# schematic_1_3.net
KiCad netlist of a schematic drawn in EAGLE
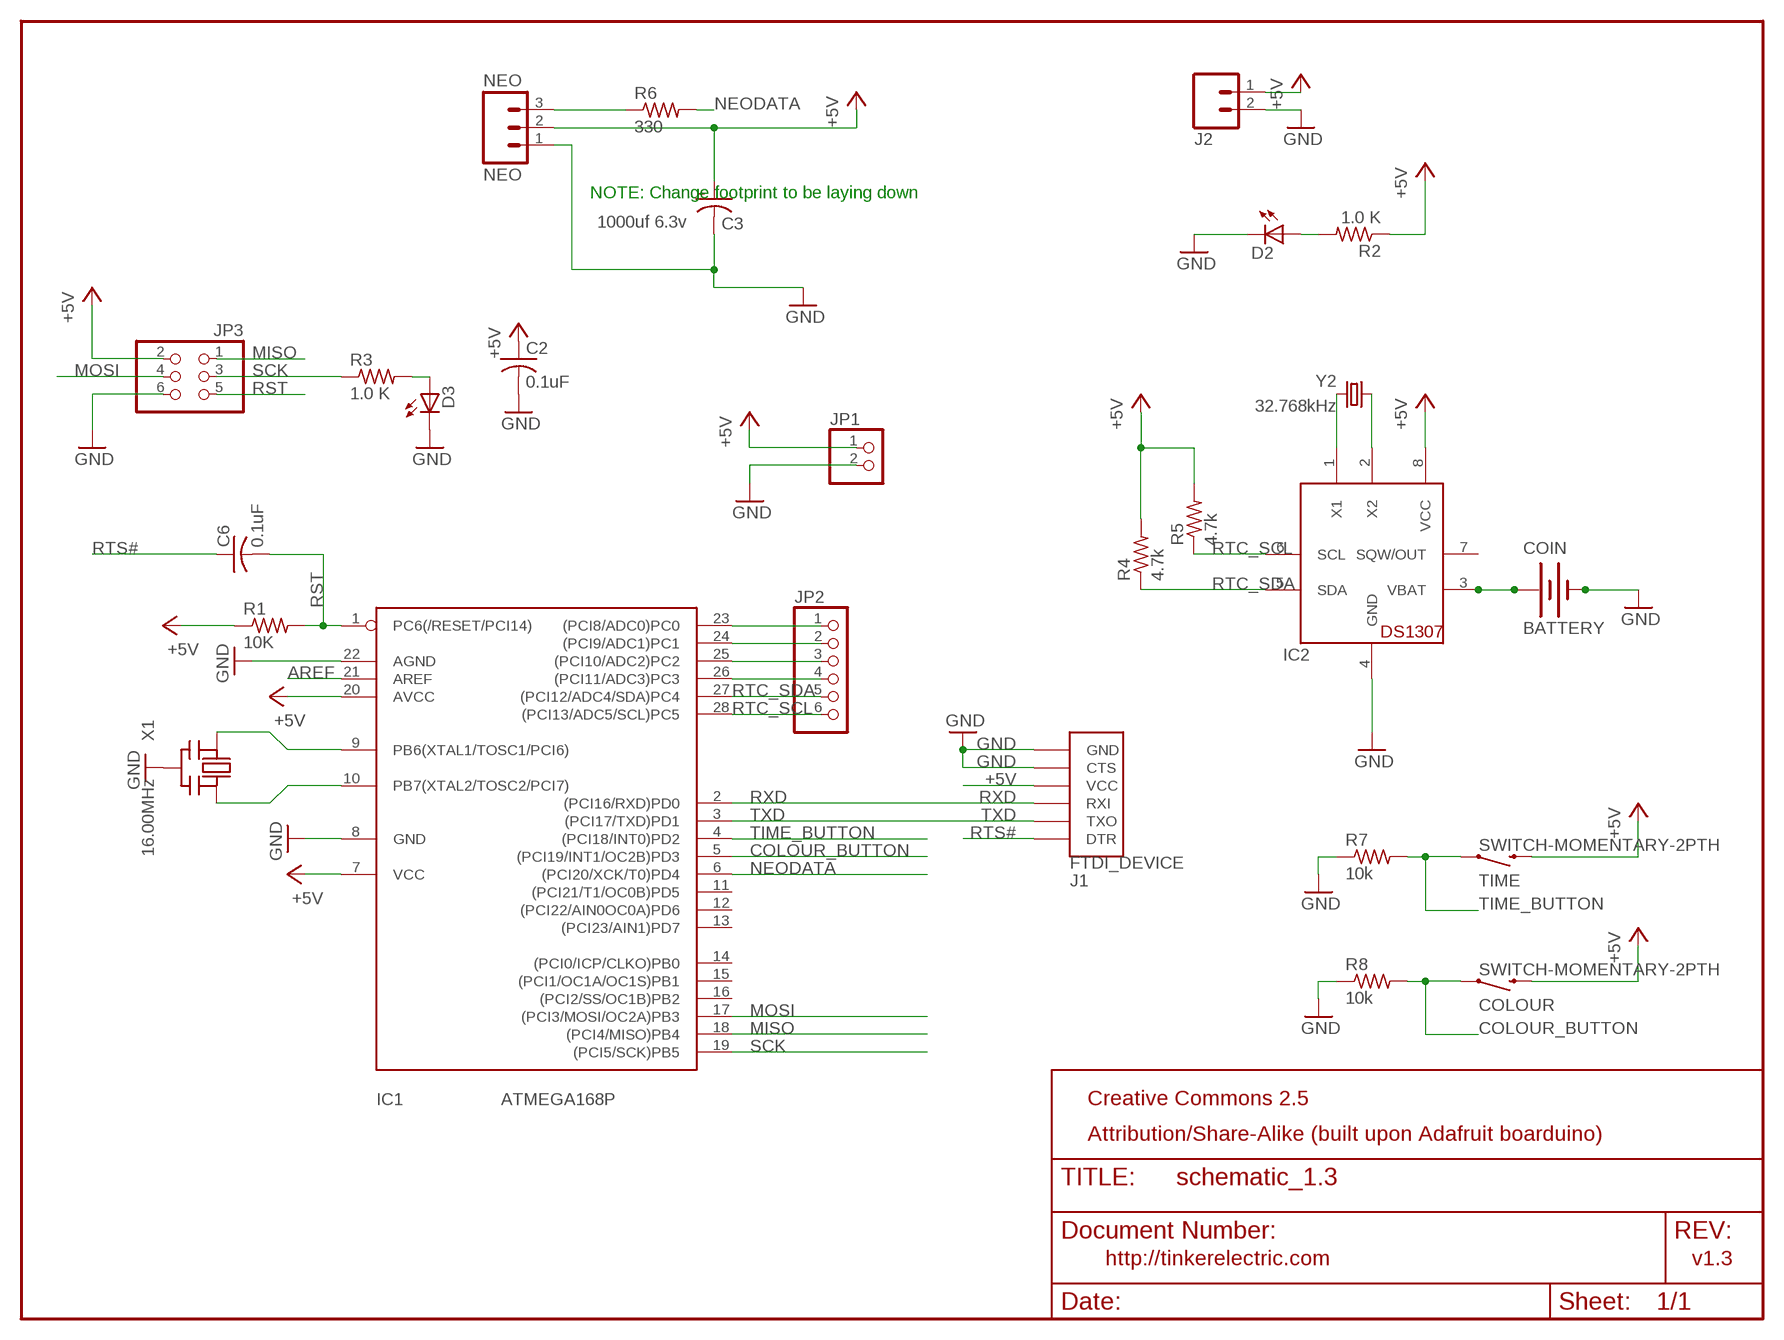
[diagram p0: schematic, sheet 1]

(export (version "E")
  (design (tool "Eeschema 10.0.6"))
  (components
    (comp (ref "C2")
      (value "0.1uF")
      (footprint "eagle-import:C025-025X050")
      (libsource (lib "eagle-import") (part "C-US025-025X050"))
    )
    (comp (ref "C3")
      (value "1000uf 6.3v")
      (footprint "eagle-import:E5-10,5")
      (libsource (lib "eagle-import") (part "CPOL-USE5-10.5"))
    )
    (comp (ref "C6")
      (value "0.1uF")
      (footprint "eagle-import:C025-025X050")
      (libsource (lib "eagle-import") (part "C-US025-025X050"))
    )
    (comp (ref "COIN")
      (value "BATTERY")
      (footprint "eagle-import:BATTCOM_12MM")
      (libsource (lib "eagle-import") (part "BATTERY"))
    )
    (comp (ref "COLOUR")
      (value "SWITCH-MOMENTARY-2PTH")
      (footprint "eagle-import:TACTILE-PTH")
      (libsource (lib "eagle-import") (part "SWITCH-MOMENTARY-2PTH"))
    )
    (comp (ref "D2")
      (value "LED3MM")
      (footprint "eagle-import:LED3MM")
      (libsource (lib "eagle-import") (part "LED3MM"))
    )
    (comp (ref "D3")
      (value "Green")
      (footprint "eagle-import:LED3MM")
      (libsource (lib "eagle-import") (part "LED3MM"))
    )
    (comp (ref "IC1")
      (value "ATMEGA168P")
      (footprint "eagle-import:DIL28_3")
      (libsource (lib "eagle-import") (part "ATMEGA168PROUND"))
    )
    (comp (ref "IC2")
      (value "DS1307")
      (footprint "eagle-import:DIL08")
      (libsource (lib "eagle-import") (part "DS1307"))
    )
    (comp (ref "J1")
      (value "FTDI_DEVICE")
      (footprint "eagle-import:FTDI_DEVICE_SIDE")
      (libsource (lib "eagle-import") (part "FTDI_DEVICE"))
    )
    (comp (ref "J2")
      (value "M02POLAR")
      (footprint "eagle-import:MOLEX-1X2")
      (libsource (lib "eagle-import") (part "M02POLAR"))
    )
    (comp (ref "JP1")
      (value "PINHD-1X2CB")
      (footprint "eagle-import:1X02-CB")
      (libsource (lib "eagle-import") (part "PINHD-1X2CB"))
    )
    (comp (ref "JP2")
      (value "PINHD-1X6CB")
      (footprint "eagle-import:1X06-CLEANBIG")
      (libsource (lib "eagle-import") (part "PINHD-1X6CB"))
    )
    (comp (ref "JP3")
      (value "PINHD-2X3")
      (footprint "eagle-import:2X03")
      (libsource (lib "eagle-import") (part "PINHD-2X3"))
    )
    (comp (ref "NEO")
      (value "NEO")
      (footprint "eagle-import:MOLEX-1X3")
      (libsource (lib "eagle-import") (part "M03POLAR"))
    )
    (comp (ref "R1")
      (value "10K")
      (footprint "eagle-import:0204V")
      (libsource (lib "eagle-import") (part "R-US_0204/2V"))
    )
    (comp (ref "R2")
      (value "1.0 K")
      (footprint "eagle-import:0204V")
      (libsource (lib "eagle-import") (part "R-US_0204/2V"))
    )
    (comp (ref "R3")
      (value "1.0 K")
      (footprint "eagle-import:0204V")
      (libsource (lib "eagle-import") (part "R-US_0204/2V"))
    )
    (comp (ref "R4")
      (value "4.7k")
      (footprint "eagle-import:0204V")
      (libsource (lib "eagle-import") (part "R-US_0204/2V"))
    )
    (comp (ref "R5")
      (value "4.7k")
      (footprint "eagle-import:0204V")
      (libsource (lib "eagle-import") (part "R-US_0204/2V"))
    )
    (comp (ref "R6")
      (value "330")
      (footprint "eagle-import:0204V")
      (libsource (lib "eagle-import") (part "R-US_0204/2V"))
    )
    (comp (ref "R7")
      (value "10k")
      (footprint "eagle-import:0204V")
      (libsource (lib "eagle-import") (part "R-US_0204/2V"))
    )
    (comp (ref "R8")
      (value "10k")
      (footprint "eagle-import:0204V")
      (libsource (lib "eagle-import") (part "R-US_0204/2V"))
    )
    (comp (ref "TIME")
      (value "SWITCH-MOMENTARY-2PTH")
      (footprint "eagle-import:TACTILE-PTH")
      (libsource (lib "eagle-import") (part "SWITCH-MOMENTARY-2PTH"))
    )
    (comp (ref "X1")
      (value "16.00MHz")
      (footprint "eagle-import:CERM_OSC")
      (libsource (lib "eagle-import") (part "CERMOSCILL"))
    )
    (comp (ref "Y2")
      (value "32.768kHz")
      (footprint "eagle-import:TC26HEZ")
      (libsource (lib "eagle-import") (part "CRYSTALTC26H_EZ"))
    )
  )
  (nets
    (net (code "1") (name "+5V") (class "Default")
      (node (ref "C2") (pin "1") (pinfunction "1_1") (pintype "passive"))
      (node (ref "C3") (pin "+") (pinfunction "+_+") (pintype "passive"))
      (node (ref "COLOUR") (pin "3") (pinfunction "2_3") (pintype "passive"))
      (node (ref "IC1") (pin "20") (pinfunction "AVCC_20") (pintype "bidirectional"))
      (node (ref "IC1") (pin "7") (pinfunction "VCC_7") (pintype "bidirectional"))
      (node (ref "IC2") (pin "8") (pinfunction "VCC_8") (pintype "power_in"))
      (node (ref "J1") (pin "P$4") (pinfunction "VCC_P$4") (pintype "bidirectional"))
      (node (ref "J2") (pin "1") (pinfunction "1_1") (pintype "passive"))
      (node (ref "JP1") (pin "1") (pinfunction "1_1") (pintype "passive"))
      (node (ref "JP3") (pin "2") (pinfunction "2_2") (pintype "passive"))
      (node (ref "NEO") (pin "2") (pinfunction "2_2") (pintype "passive"))
      (node (ref "R1") (pin "1") (pinfunction "1_1") (pintype "passive"))
      (node (ref "R2") (pin "1") (pinfunction "1_1") (pintype "passive"))
      (node (ref "R4") (pin "2") (pinfunction "2_2") (pintype "passive"))
      (node (ref "R5") (pin "2") (pinfunction "2_2") (pintype "passive"))
      (node (ref "TIME") (pin "3") (pinfunction "2_3") (pintype "passive"))
    )
    (net (code "2") (name "/AREF") (class "Default")
      (node (ref "IC1") (pin "21") (pinfunction "AREF_21") (pintype "bidirectional"))
    )
    (net (code "3") (name "/COLOUR_BUTTON") (class "Default")
      (node (ref "COLOUR") (pin "1") (pinfunction "1_1") (pintype "passive"))
      (node (ref "IC1") (pin "5") (pinfunction "(PCI19/INT1/OC2B)PD3_5") (pintype "bidirectional"))
      (node (ref "R8") (pin "2") (pinfunction "2_2") (pintype "passive"))
    )
    (net (code "4") (name "/MISO") (class "Default")
      (node (ref "IC1") (pin "18") (pinfunction "(PCI4/MISO)PB4_18") (pintype "bidirectional"))
      (node (ref "JP3") (pin "1") (pinfunction "1_1") (pintype "passive"))
    )
    (net (code "5") (name "/MOSI") (class "Default")
      (node (ref "IC1") (pin "17") (pinfunction "(PCI3/MOSI/OC2A)PB3_17") (pintype "bidirectional"))
      (node (ref "JP3") (pin "4") (pinfunction "4_4") (pintype "passive"))
    )
    (net (code "6") (name "/NEODATA") (class "Default")
      (node (ref "IC1") (pin "6") (pinfunction "(PCI20/XCK/T0)PD4_6") (pintype "bidirectional"))
      (node (ref "R6") (pin "2") (pinfunction "2_2") (pintype "passive"))
    )
    (net (code "7") (name "/RST") (class "Default")
      (node (ref "C6") (pin "2") (pinfunction "2_2") (pintype "passive"))
      (node (ref "IC1") (pin "1") (pinfunction "PC6(/RESET/PCI14)_1") (pintype "bidirectional"))
      (node (ref "JP3") (pin "5") (pinfunction "5_5") (pintype "passive"))
      (node (ref "R1") (pin "2") (pinfunction "2_2") (pintype "passive"))
    )
    (net (code "8") (name "/RTC_SCL") (class "Default")
      (node (ref "IC1") (pin "28") (pinfunction "(PCI13/ADC5/SCL)PC5_28") (pintype "bidirectional"))
      (node (ref "IC2") (pin "6") (pinfunction "SCL_6") (pintype "bidirectional"))
      (node (ref "JP2") (pin "6") (pinfunction "6_6") (pintype "passive"))
      (node (ref "R5") (pin "1") (pinfunction "1_1") (pintype "passive"))
    )
    (net (code "9") (name "/RTC_SDA") (class "Default")
      (node (ref "IC1") (pin "27") (pinfunction "(PCI12/ADC4/SDA)PC4_27") (pintype "bidirectional"))
      (node (ref "IC2") (pin "5") (pinfunction "SDA_5") (pintype "bidirectional"))
      (node (ref "JP2") (pin "5") (pinfunction "5_5") (pintype "passive"))
      (node (ref "R4") (pin "1") (pinfunction "1_1") (pintype "passive"))
    )
    (net (code "10") (name "/RTS#") (class "Default")
      (node (ref "C6") (pin "1") (pinfunction "1_1") (pintype "passive"))
      (node (ref "J1") (pin "P$1") (pinfunction "DTR_P$1") (pintype "bidirectional"))
    )
    (net (code "11") (name "/RXD") (class "Default")
      (node (ref "IC1") (pin "2") (pinfunction "(PCI16/RXD)PD0_2") (pintype "bidirectional"))
      (node (ref "J1") (pin "P$3") (pinfunction "RXI_P$3") (pintype "bidirectional"))
    )
    (net (code "12") (name "/SCK") (class "Default")
      (node (ref "IC1") (pin "19") (pinfunction "(PCI5/SCK)PB5_19") (pintype "bidirectional"))
      (node (ref "JP3") (pin "3") (pinfunction "3_3") (pintype "passive"))
      (node (ref "R3") (pin "1") (pinfunction "1_1") (pintype "passive"))
    )
    (net (code "13") (name "/TIME_BUTTON") (class "Default")
      (node (ref "IC1") (pin "4") (pinfunction "(PCI18/INT0)PD2_4") (pintype "bidirectional"))
      (node (ref "R7") (pin "2") (pinfunction "2_2") (pintype "passive"))
      (node (ref "TIME") (pin "1") (pinfunction "1_1") (pintype "passive"))
    )
    (net (code "14") (name "/TXD") (class "Default")
      (node (ref "IC1") (pin "3") (pinfunction "(PCI17/TXD)PD1_3") (pintype "bidirectional"))
      (node (ref "J1") (pin "P$2") (pinfunction "TXO_P$2") (pintype "bidirectional"))
    )
    (net (code "15") (name "GND") (class "Default")
      (node (ref "C2") (pin "2") (pinfunction "2_2") (pintype "passive"))
      (node (ref "C3") (pin "-") (pinfunction "-_-") (pintype "passive"))
      (node (ref "COIN") (pin "-") (pinfunction "-_-") (pintype "power_in"))
      (node (ref "D2") (pin "K") (pinfunction "C_K") (pintype "passive"))
      (node (ref "D3") (pin "K") (pinfunction "C_K") (pintype "passive"))
      (node (ref "IC1") (pin "22") (pinfunction "AGND_22") (pintype "bidirectional"))
      (node (ref "IC1") (pin "8") (pinfunction "GND_8") (pintype "bidirectional"))
      (node (ref "IC2") (pin "4") (pinfunction "GND_4") (pintype "power_in"))
      (node (ref "J1") (pin "P$5") (pinfunction "CTS_P$5") (pintype "bidirectional"))
      (node (ref "J1") (pin "P$6") (pinfunction "GND_P$6") (pintype "bidirectional"))
      (node (ref "J2") (pin "2") (pinfunction "2_2") (pintype "passive"))
      (node (ref "JP1") (pin "2") (pinfunction "2_2") (pintype "passive"))
      (node (ref "JP3") (pin "6") (pinfunction "6_6") (pintype "passive"))
      (node (ref "NEO") (pin "1") (pinfunction "1_1") (pintype "passive"))
      (node (ref "R7") (pin "1") (pinfunction "1_1") (pintype "passive"))
      (node (ref "R8") (pin "1") (pinfunction "1_1") (pintype "passive"))
      (node (ref "X1") (pin "P$2") (pinfunction "GND_P$2") (pintype "bidirectional"))
    )
    (net (code "16") (name "Net-(D2-PadA)") (class "Default")
      (node (ref "D2") (pin "A") (pinfunction "A_A") (pintype "passive"))
      (node (ref "R2") (pin "2") (pinfunction "2_2") (pintype "passive"))
    )
    (net (code "17") (name "Net-(D3-PadA)") (class "Default")
      (node (ref "D3") (pin "A") (pinfunction "A_A") (pintype "passive"))
      (node (ref "R3") (pin "2") (pinfunction "2_2") (pintype "passive"))
    )
    (net (code "18") (name "Net-(IC1-(PCI8{slash}ADC0)PC0)") (class "Default")
      (node (ref "IC1") (pin "23") (pinfunction "(PCI8/ADC0)PC0_23") (pintype "bidirectional"))
      (node (ref "JP2") (pin "1") (pinfunction "1_1") (pintype "passive"))
    )
    (net (code "19") (name "Net-(IC1-(PCI9{slash}ADC1)PC1)") (class "Default")
      (node (ref "IC1") (pin "24") (pinfunction "(PCI9/ADC1)PC1_24") (pintype "bidirectional"))
      (node (ref "JP2") (pin "2") (pinfunction "2_2") (pintype "passive"))
    )
    (net (code "20") (name "Net-(IC1-(PCI10{slash}ADC2)PC2)") (class "Default")
      (node (ref "IC1") (pin "25") (pinfunction "(PCI10/ADC2)PC2_25") (pintype "bidirectional"))
      (node (ref "JP2") (pin "3") (pinfunction "3_3") (pintype "passive"))
    )
    (net (code "21") (name "Net-(IC1-(PCI11{slash}ADC3)PC3)") (class "Default")
      (node (ref "IC1") (pin "26") (pinfunction "(PCI11/ADC3)PC3_26") (pintype "bidirectional"))
      (node (ref "JP2") (pin "4") (pinfunction "4_4") (pintype "passive"))
    )
    (net (code "22") (name "Net-(IC1-PB6(XTAL1{slash}TOSC1{slash}PCI6))") (class "Default")
      (node (ref "IC1") (pin "9") (pinfunction "PB6(XTAL1/TOSC1/PCI6)_9") (pintype "bidirectional"))
      (node (ref "X1") (pin "P$1") (pinfunction "IN_P$1") (pintype "bidirectional"))
    )
    (net (code "23") (name "Net-(IC1-PB7(XTAL2{slash}TOSC2{slash}PCI7))") (class "Default")
      (node (ref "IC1") (pin "10") (pinfunction "PB7(XTAL2/TOSC2/PCI7)_10") (pintype "bidirectional"))
      (node (ref "X1") (pin "P$3") (pinfunction "OUT_P$3") (pintype "bidirectional"))
    )
    (net (code "24") (name "Net-(IC2-VBAT)") (class "Default")
      (node (ref "COIN") (pin "+") (pinfunction "+_+") (pintype "power_in"))
      (node (ref "IC2") (pin "3") (pinfunction "VBAT_3") (pintype "power_in"))
    )
    (net (code "25") (name "Net-(IC2-X1)") (class "Default")
      (node (ref "IC2") (pin "1") (pinfunction "X1_1") (pintype "passive"))
      (node (ref "Y2") (pin "2") (pinfunction "2_2") (pintype "passive"))
    )
    (net (code "26") (name "Net-(IC2-X2)") (class "Default")
      (node (ref "IC2") (pin "2") (pinfunction "X2_2") (pintype "passive"))
      (node (ref "Y2") (pin "1") (pinfunction "1_1") (pintype "passive"))
    )
    (net (code "27") (name "Net-(NEO-Pad3)") (class "Default")
      (node (ref "NEO") (pin "3") (pinfunction "3_3") (pintype "passive"))
      (node (ref "R6") (pin "1") (pinfunction "1_1") (pintype "passive"))
    )
    (net (code "28") (name "unconnected-(IC1-(PCI0{slash}ICP{slash}CLKO)PB0-Pad14)") (class "Default")
      (node (ref "IC1") (pin "14") (pinfunction "(PCI0/ICP/CLKO)PB0_14") (pintype "bidirectional"))
    )
    (net (code "29") (name "unconnected-(IC1-(PCI1{slash}OC1A{slash}OC1S)PB1-Pad15)") (class "Default")
      (node (ref "IC1") (pin "15") (pinfunction "(PCI1/OC1A/OC1S)PB1_15") (pintype "bidirectional"))
    )
    (net (code "30") (name "unconnected-(IC1-(PCI2{slash}SS{slash}OC1B)PB2-Pad16)") (class "Default")
      (node (ref "IC1") (pin "16") (pinfunction "(PCI2/SS/OC1B)PB2_16") (pintype "bidirectional"))
    )
    (net (code "31") (name "unconnected-(IC1-(PCI21{slash}T1{slash}OC0B)PD5-Pad11)") (class "Default")
      (node (ref "IC1") (pin "11") (pinfunction "(PCI21/T1/OC0B)PD5_11") (pintype "bidirectional"))
    )
    (net (code "32") (name "unconnected-(IC1-(PCI22{slash}AIN0OC0A)PD6-Pad12)") (class "Default")
      (node (ref "IC1") (pin "12") (pinfunction "(PCI22/AIN0OC0A)PD6_12") (pintype "bidirectional"))
    )
    (net (code "33") (name "unconnected-(IC1-(PCI23{slash}AIN1)PD7-Pad13)") (class "Default")
      (node (ref "IC1") (pin "13") (pinfunction "(PCI23/AIN1)PD7_13") (pintype "bidirectional"))
    )
    (net (code "34") (name "unconnected-(IC2-SQW{slash}OUT-Pad7)") (class "Default")
      (node (ref "IC2") (pin "7") (pinfunction "SQW/OUT_7") (pintype "bidirectional"))
    )
  )
)
